# Lab1_PowerSupply.net
KiCad netlist of a schematic drawn in Altium Designer
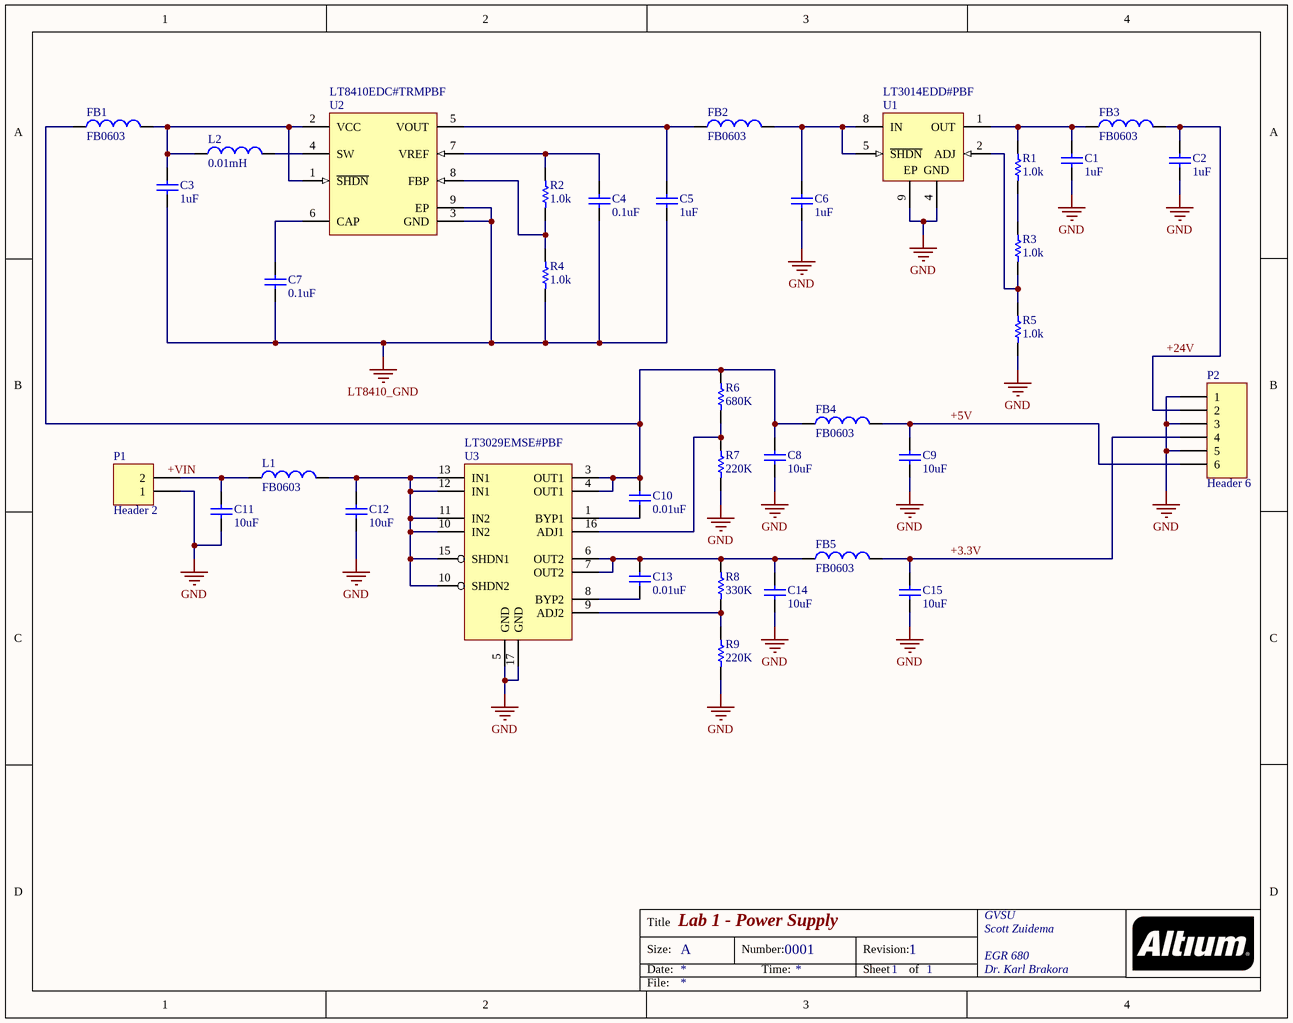
[diagram p0: Lab1_PowerSupply.SchDoc]

(export (version "E")
  (design (tool "Eeschema 10.0.6"))
  (components
    (comp (ref "C1")
      (value "1uF")
      (footprint "0805CAP")
      (description "0805 Ceramic Chip Capacitor - Standard")
      (fields (field (name "Comment") "C0805"))
      (libsource (lib "Standard Components") (part "C0805"))
    )
    (comp (ref "C2")
      (value "1uF")
      (footprint "0805CAP")
      (description "0805 Ceramic Chip Capacitor - Standard")
      (fields (field (name "Comment") "C0805"))
      (libsource (lib "Standard Components") (part "C0805"))
    )
    (comp (ref "C3")
      (value "1uF")
      (footprint "0805CAP")
      (description "0805 Ceramic Chip Capacitor - Standard")
      (fields (field (name "Comment") "C0805"))
      (libsource (lib "Standard Components") (part "C0805"))
    )
    (comp (ref "C4")
      (value "0.1uF")
      (footprint "0603CAP")
      (description "0603 Ceramic Chip Capacitor - Standard")
      (fields (field (name "Comment") "C0603"))
      (libsource (lib "Standard Components") (part "C0603"))
    )
    (comp (ref "C5")
      (value "1uF")
      (footprint "0805CAP")
      (description "0805 Ceramic Chip Capacitor - Standard")
      (fields (field (name "Comment") "C0805"))
      (libsource (lib "Standard Components") (part "C0805"))
    )
    (comp (ref "C6")
      (value "1uF")
      (footprint "0805CAP")
      (description "0805 Ceramic Chip Capacitor - Standard")
      (fields (field (name "Comment") "C0805"))
      (libsource (lib "Standard Components") (part "C0805"))
    )
    (comp (ref "C7")
      (value "0.1uF")
      (footprint "0603CAP")
      (description "0603 Ceramic Chip Capacitor - Standard")
      (fields (field (name "Comment") "C0603"))
      (libsource (lib "Standard Components") (part "C0603"))
    )
    (comp (ref "C8")
      (value "10uF")
      (footprint "0805CAP")
      (description "0805 Ceramic Chip Capacitor - Standard")
      (fields (field (name "Comment") "C0805"))
      (libsource (lib "Standard Components") (part "C0805"))
    )
    (comp (ref "C9")
      (value "10uF")
      (footprint "0805CAP")
      (description "0805 Ceramic Chip Capacitor - Standard")
      (fields (field (name "Comment") "C0805"))
      (libsource (lib "Standard Components") (part "C0805"))
    )
    (comp (ref "C10")
      (value "0.01uF")
      (footprint "0603CAP")
      (description "0603 Ceramic Chip Capacitor - Standard")
      (fields (field (name "Comment") "C0603"))
      (libsource (lib "Standard Components") (part "C0603"))
    )
    (comp (ref "C11")
      (value "10uF")
      (footprint "0805CAP")
      (description "0805 Ceramic Chip Capacitor - Standard")
      (fields (field (name "Comment") "C0805"))
      (libsource (lib "Standard Components") (part "C0805"))
    )
    (comp (ref "C12")
      (value "10uF")
      (footprint "0805CAP")
      (description "0805 Ceramic Chip Capacitor - Standard")
      (fields (field (name "Comment") "C0805"))
      (libsource (lib "Standard Components") (part "C0805"))
    )
    (comp (ref "C13")
      (value "0.01uF")
      (footprint "0603CAP")
      (description "0603 Ceramic Chip Capacitor - Standard")
      (fields (field (name "Comment") "C0603"))
      (libsource (lib "Standard Components") (part "C0603"))
    )
    (comp (ref "C14")
      (value "10uF")
      (footprint "0805CAP")
      (description "0805 Ceramic Chip Capacitor - Standard")
      (fields (field (name "Comment") "C0805"))
      (libsource (lib "Standard Components") (part "C0805"))
    )
    (comp (ref "C15")
      (value "10uF")
      (footprint "0805CAP")
      (description "0805 Ceramic Chip Capacitor - Standard")
      (fields (field (name "Comment") "C0805"))
      (libsource (lib "Standard Components") (part "C0805"))
    )
    (comp (ref "FB1")
      (value "FB0603")
      (footprint "0603CAP")
      (description "0603 Multilayer Ferrite Power Bead")
      (fields (field (name "MANUFACTURER") "KOA Speer"))
      (libsource (lib "Standard Components") (part "FB0603"))
    )
    (comp (ref "FB2")
      (value "FB0603")
      (footprint "0603CAP")
      (description "0603 Multilayer Ferrite Power Bead")
      (fields (field (name "MANUFACTURER") "KOA Speer"))
      (libsource (lib "Standard Components") (part "FB0603"))
    )
    (comp (ref "FB3")
      (value "FB0603")
      (footprint "0603CAP")
      (description "0603 Multilayer Ferrite Power Bead")
      (fields (field (name "MANUFACTURER") "KOA Speer"))
      (libsource (lib "Standard Components") (part "FB0603"))
    )
    (comp (ref "FB4")
      (value "FB0603")
      (footprint "0603CAP")
      (description "0603 Multilayer Ferrite Power Bead")
      (fields (field (name "MANUFACTURER") "KOA Speer"))
      (libsource (lib "Standard Components") (part "FB0603"))
    )
    (comp (ref "FB5")
      (value "FB0603")
      (footprint "0603CAP")
      (description "0603 Multilayer Ferrite Power Bead")
      (fields (field (name "MANUFACTURER") "KOA Speer"))
      (libsource (lib "Standard Components") (part "FB0603"))
    )
    (comp (ref "L1")
      (value "FB0603")
      (footprint "0603CAP")
      (description "0603 Multilayer Ferrite Power Bead")
      (fields (field (name "MANUFACTURER") "KOA Speer"))
      (libsource (lib "Standard Components") (part "FB0603"))
    )
    (comp (ref "L2")
      (value "0.01mH")
      (footprint "1210RES")
      (description "1210 Chip Inductor - Standard")
      (fields (field (name "Comment") "L1210"))
      (libsource (lib "Standard Components") (part "L1210"))
    )
    (comp (ref "P1")
      (value "Header 2")
      (footprint "HDR1X2")
      (description "Header, 2-Pin")
      (fields (field (name "PUBLISHER") "Altium Limited"))
      (libsource (lib "Miscellaneous Connectors") (part "Header 2"))
    )
    (comp (ref "P2")
      (value "Header 6")
      (footprint "HDR1X6")
      (description "Header, 6-Pin")
      (fields (field (name "PUBLISHER") "Altium Limited"))
      (libsource (lib "Miscellaneous Connectors") (part "Header 6"))
    )
    (comp (ref "R1")
      (value "1.0k")
      (footprint "0402RES")
      (description "0402 Chip Resistor - Standard")
      (fields (field (name "Comment") "R0402"))
      (libsource (lib "Standard Components") (part "R0402"))
    )
    (comp (ref "R2")
      (value "1.0k")
      (footprint "0402RES")
      (description "0402 Chip Resistor - Standard")
      (fields (field (name "Comment") "R0402"))
      (libsource (lib "Standard Components") (part "R0402"))
    )
    (comp (ref "R3")
      (value "1.0k")
      (footprint "0402RES")
      (description "0402 Chip Resistor - Standard")
      (fields (field (name "Comment") "R0402"))
      (libsource (lib "Standard Components") (part "R0402"))
    )
    (comp (ref "R4")
      (value "1.0k")
      (footprint "0402RES")
      (description "0402 Chip Resistor - Standard")
      (fields (field (name "Comment") "R0402"))
      (libsource (lib "Standard Components") (part "R0402"))
    )
    (comp (ref "R5")
      (value "1.0k")
      (footprint "0402RES")
      (description "0402 Chip Resistor - Standard")
      (fields (field (name "Comment") "R0402"))
      (libsource (lib "Standard Components") (part "R0402"))
    )
    (comp (ref "R6")
      (value "680K")
      (footprint "0402RES")
      (description "0402 Chip Resistor - Standard")
      (fields (field (name "Comment") "R0402"))
      (libsource (lib "Standard Components") (part "R0402"))
    )
    (comp (ref "R7")
      (value "220K")
      (footprint "0402RES")
      (description "0402 Chip Resistor - Standard")
      (fields (field (name "Comment") "R0402"))
      (libsource (lib "Standard Components") (part "R0402"))
    )
    (comp (ref "R8")
      (value "330K")
      (footprint "0402RES")
      (description "0402 Chip Resistor - Standard")
      (fields (field (name "Comment") "R0402"))
      (libsource (lib "Standard Components") (part "R0402"))
    )
    (comp (ref "R9")
      (value "220K")
      (footprint "0402RES")
      (description "0402 Chip Resistor - Standard")
      (fields (field (name "Comment") "R0402"))
      (libsource (lib "Standard Components") (part "R0402"))
    )
    (comp (ref "U1")
      (value "LT3014EDD#PBF")
      (footprint "LT-DD-8_V")
      (fields (field (name "MANUFACTURER") "Linear Technology"))
      (libsource (lib "LinearTechnologies") (part "LT3014EDD#PBF"))
    )
    (comp (ref "U2")
      (value "LT8410EDC#TRMPBF")
      (footprint "LT-DC8_V")
      (fields (field (name "MANUFACTURER") "Linear Technology"))
      (libsource (lib "LinearTechnologies") (part "LT8410EDC#TRMPBF"))
    )
    (comp (ref "U3")
      (value "LDO")
      (footprint "MSE16")
      (description "Dual 500mA/500mA, Low Dropout, Low Noise, Micropower Linear Regulator")
      (fields
        (field (name "MANUFACTURER") "Linear Technologies")
        (field (name "MANUFACTURER P/N") "LT3029EMSE#PBF")
      )
      (libsource (lib "LinearTechnologies") (part "LT3029MSE"))
    )
  )
  (nets
    (net (code "1") (name "/+3.3V") (class "Default")
      (node (ref "C15") (pin "2") (pinfunction "2_2") (pintype "passive"))
      (node (ref "FB5") (pin "2") (pinfunction "2_2") (pintype "passive"))
      (node (ref "P2") (pin "4") (pinfunction "4_4") (pintype "passive"))
    )
    (net (code "2") (name "/+5V") (class "Default")
      (node (ref "C9") (pin "2") (pinfunction "2_2") (pintype "passive"))
      (node (ref "FB4") (pin "2") (pinfunction "2_2") (pintype "passive"))
      (node (ref "P2") (pin "6") (pinfunction "6_6") (pintype "passive"))
    )
    (net (code "3") (name "/+24V") (class "Default")
      (node (ref "C2") (pin "2") (pinfunction "2_2") (pintype "passive"))
      (node (ref "FB3") (pin "2") (pinfunction "2_2") (pintype "passive"))
      (node (ref "P2") (pin "2") (pinfunction "2_2") (pintype "passive"))
    )
    (net (code "5") (name "GND") (class "Default")
      (node (ref "C1") (pin "1") (pinfunction "1_1") (pintype "passive"))
      (node (ref "C11") (pin "1") (pinfunction "1_1") (pintype "passive"))
      (node (ref "C12") (pin "1") (pinfunction "1_1") (pintype "passive"))
      (node (ref "C14") (pin "1") (pinfunction "1_1") (pintype "passive"))
      (node (ref "C15") (pin "1") (pinfunction "1_1") (pintype "passive"))
      (node (ref "C2") (pin "1") (pinfunction "1_1") (pintype "passive"))
      (node (ref "C6") (pin "1") (pinfunction "1_1") (pintype "passive"))
      (node (ref "C8") (pin "1") (pinfunction "1_1") (pintype "passive"))
      (node (ref "C9") (pin "1") (pinfunction "1_1") (pintype "passive"))
      (node (ref "P1") (pin "1") (pinfunction "1_1") (pintype "passive"))
      (node (ref "P2") (pin "1") (pinfunction "1_1") (pintype "passive"))
      (node (ref "P2") (pin "3") (pinfunction "3_3") (pintype "passive"))
      (node (ref "P2") (pin "5") (pinfunction "5_5") (pintype "passive"))
      (node (ref "R5") (pin "1") (pinfunction "1_1") (pintype "passive"))
      (node (ref "R7") (pin "1") (pinfunction "1_1") (pintype "passive"))
      (node (ref "R9") (pin "1") (pinfunction "1_1") (pintype "passive"))
      (node (ref "U1") (pin "4") (pinfunction "GND_4") (pintype "power_in"))
      (node (ref "U1") (pin "9") (pinfunction "EP_9") (pintype "power_in"))
      (node (ref "U3") (pin "17") (pinfunction "GND_17") (pintype "passive"))
      (node (ref "U3") (pin "5") (pinfunction "GND_5") (pintype "passive"))
    )
    (net (code "6") (name "LT8410_GND") (class "Default")
      (node (ref "C3") (pin "1") (pinfunction "1_1") (pintype "passive"))
      (node (ref "C4") (pin "1") (pinfunction "1_1") (pintype "passive"))
      (node (ref "C5") (pin "1") (pinfunction "1_1") (pintype "passive"))
      (node (ref "C7") (pin "1") (pinfunction "1_1") (pintype "passive"))
      (node (ref "R4") (pin "1") (pinfunction "1_1") (pintype "passive"))
      (node (ref "U2") (pin "3") (pinfunction "GND_3") (pintype "power_in"))
      (node (ref "U2") (pin "9") (pinfunction "EP_9") (pintype "power_in"))
    )
    (net (code "7") (name "Net-(C10-Pad2)") (class "Default")
      (node (ref "C10") (pin "2") (pinfunction "2_2") (pintype "passive"))
      (node (ref "C8") (pin "2") (pinfunction "2_2") (pintype "passive"))
      (node (ref "FB1") (pin "1") (pinfunction "1_1") (pintype "passive"))
      (node (ref "FB4") (pin "1") (pinfunction "1_1") (pintype "passive"))
      (node (ref "R6") (pin "2") (pinfunction "2_2") (pintype "passive"))
      (node (ref "U3") (pin "3") (pinfunction "OUT1_3") (pintype "passive"))
      (node (ref "U3") (pin "4") (pinfunction "OUT1_4") (pintype "passive"))
    )
    (net (code "8") (name "Net-(C11-Pad2)") (class "Default")
      (node (ref "C11") (pin "2") (pinfunction "2_2") (pintype "passive"))
      (node (ref "L1") (pin "1") (pinfunction "1_1") (pintype "passive"))
      (node (ref "P1") (pin "2") (pinfunction "2_2") (pintype "passive"))
    )
    (net (code "9") (name "Net-(C13-Pad2)") (class "Default")
      (node (ref "C13") (pin "2") (pinfunction "2_2") (pintype "passive"))
      (node (ref "C14") (pin "2") (pinfunction "2_2") (pintype "passive"))
      (node (ref "FB5") (pin "1") (pinfunction "1_1") (pintype "passive"))
      (node (ref "R8") (pin "2") (pinfunction "2_2") (pintype "passive"))
      (node (ref "U3") (pin "6") (pinfunction "OUT2_6") (pintype "passive"))
      (node (ref "U3") (pin "7") (pinfunction "OUT2_7") (pintype "passive"))
    )
    (net (code "10") (name "Net-(R1-Pad1)") (class "Default")
      (node (ref "R1") (pin "1") (pinfunction "1_1") (pintype "passive"))
      (node (ref "R3") (pin "2") (pinfunction "2_2") (pintype "passive"))
    )
    (net (code "11") (name "Net-(U1-ADJ)") (class "Default")
      (node (ref "R3") (pin "1") (pinfunction "1_1") (pintype "passive"))
      (node (ref "R5") (pin "2") (pinfunction "2_2") (pintype "passive"))
      (node (ref "U1") (pin "2") (pinfunction "ADJ_2") (pintype "input"))
    )
    (net (code "12") (name "Net-(U1-IN)") (class "Default")
      (node (ref "C6") (pin "2") (pinfunction "2_2") (pintype "passive"))
      (node (ref "FB2") (pin "2") (pinfunction "2_2") (pintype "passive"))
      (node (ref "U1") (pin "5") (pinfunction "~{SHDN}_5") (pintype "input"))
      (node (ref "U1") (pin "8") (pinfunction "IN_8") (pintype "power_in"))
    )
    (net (code "13") (name "Net-(U1-OUT)") (class "Default")
      (node (ref "C1") (pin "2") (pinfunction "2_2") (pintype "passive"))
      (node (ref "FB3") (pin "1") (pinfunction "1_1") (pintype "passive"))
      (node (ref "R1") (pin "2") (pinfunction "2_2") (pintype "passive"))
      (node (ref "U1") (pin "1") (pinfunction "OUT_1") (pintype "power_in"))
    )
    (net (code "14") (name "Net-(U2-CAP)") (class "Default")
      (node (ref "C7") (pin "2") (pinfunction "2_2") (pintype "passive"))
      (node (ref "U2") (pin "6") (pinfunction "CAP_6") (pintype "passive"))
    )
    (net (code "15") (name "Net-(U2-FBP)") (class "Default")
      (node (ref "R2") (pin "1") (pinfunction "1_1") (pintype "passive"))
      (node (ref "R4") (pin "2") (pinfunction "2_2") (pintype "passive"))
      (node (ref "U2") (pin "8") (pinfunction "FBP_8") (pintype "input"))
    )
    (net (code "16") (name "Net-(U2-SW)") (class "Default")
      (node (ref "L2") (pin "2") (pinfunction "2_2") (pintype "passive"))
      (node (ref "U2") (pin "4") (pinfunction "SW_4") (pintype "passive"))
    )
    (net (code "17") (name "Net-(U2-VCC)") (class "Default")
      (node (ref "C3") (pin "2") (pinfunction "2_2") (pintype "passive"))
      (node (ref "FB1") (pin "2") (pinfunction "2_2") (pintype "passive"))
      (node (ref "L2") (pin "1") (pinfunction "1_1") (pintype "passive"))
      (node (ref "U2") (pin "1") (pinfunction "~{SHDN}_1") (pintype "input"))
      (node (ref "U2") (pin "2") (pinfunction "VCC_2") (pintype "power_in"))
    )
    (net (code "18") (name "Net-(U2-VOUT)") (class "Default")
      (node (ref "C5") (pin "2") (pinfunction "2_2") (pintype "passive"))
      (node (ref "FB2") (pin "1") (pinfunction "1_1") (pintype "passive"))
      (node (ref "U2") (pin "5") (pinfunction "VOUT_5") (pintype "power_in"))
    )
    (net (code "19") (name "Net-(U2-VREF)") (class "Default")
      (node (ref "C4") (pin "2") (pinfunction "2_2") (pintype "passive"))
      (node (ref "R2") (pin "2") (pinfunction "2_2") (pintype "passive"))
      (node (ref "U2") (pin "7") (pinfunction "VREF_7") (pintype "input"))
    )
    (net (code "20") (name "Net-(U3-ADJ1)") (class "Default")
      (node (ref "R6") (pin "1") (pinfunction "1_1") (pintype "passive"))
      (node (ref "R7") (pin "2") (pinfunction "2_2") (pintype "passive"))
      (node (ref "U3") (pin "16") (pinfunction "ADJ1_16") (pintype "passive"))
    )
    (net (code "21") (name "Net-(U3-ADJ2)") (class "Default")
      (node (ref "R8") (pin "1") (pinfunction "1_1") (pintype "passive"))
      (node (ref "R9") (pin "2") (pinfunction "2_2") (pintype "passive"))
      (node (ref "U3") (pin "9") (pinfunction "ADJ2_9") (pintype "passive"))
    )
    (net (code "22") (name "Net-(U3-BYP1)") (class "Default")
      (node (ref "C10") (pin "1") (pinfunction "1_1") (pintype "passive"))
      (node (ref "U3") (pin "1") (pinfunction "BYP1_1") (pintype "passive"))
    )
    (net (code "23") (name "Net-(U3-BYP2)") (class "Default")
      (node (ref "C13") (pin "1") (pinfunction "1_1") (pintype "passive"))
      (node (ref "U3") (pin "8") (pinfunction "BYP2_8") (pintype "passive"))
    )
    (net (code "24") (name "Net-(U3-SHDN1)") (class "Default")
      (node (ref "C12") (pin "2") (pinfunction "2_2") (pintype "passive"))
      (node (ref "L1") (pin "2") (pinfunction "2_2") (pintype "passive"))
      (node (ref "U3") (pin "10") (pinfunction "IN2_10") (pintype "passive"))
      (node (ref "U3") (pin "11") (pinfunction "IN2_11") (pintype "passive"))
      (node (ref "U3") (pin "12") (pinfunction "IN1_12") (pintype "passive"))
      (node (ref "U3") (pin "13") (pinfunction "IN1_13") (pintype "passive"))
      (node (ref "U3") (pin "15") (pinfunction "SHDN1_15") (pintype "passive"))
    )
  )
)
